# DWS-2_Comutator.net
KiCad netlist of a schematic drawn in Altium Designer
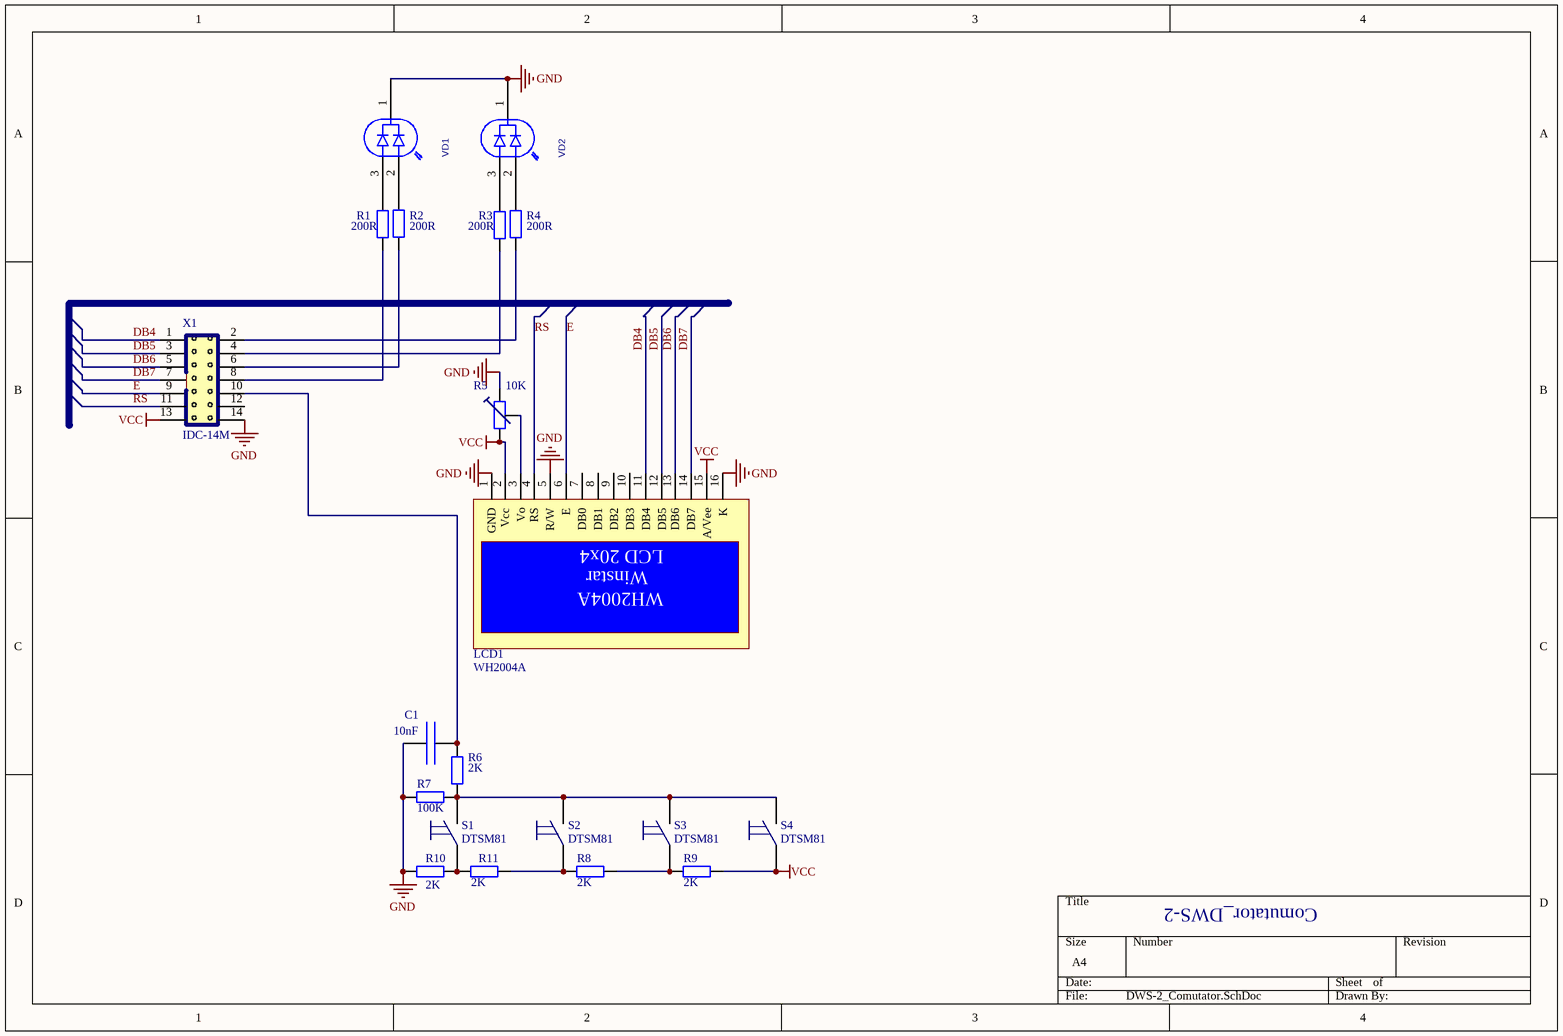
[diagram p0: DWS-2_Comutator.SchDoc]

(export (version "E")
  (design (tool "Eeschema 10.0.6"))
  (components
    (comp (ref "C1")
      (value "10nF")
      (footprint "C0805")
      (description "KONDENS_SMD")
      (libsource (lib "NEW") (part "KONDENS_SMD"))
    )
    (comp (ref "LCD1") (value "WH2004A") (footprint "WH2004A") (libsource (lib "NEW") (part "WH2004A")))
    (comp (ref "R1")
      (value "200R")
      (footprint "C0805")
      (description "Resistor")
      (fields (field (name "Comment") "RES"))
      (libsource (lib "NEW") (part "RES"))
    )
    (comp (ref "R2")
      (value "200R")
      (footprint "C0805")
      (description "Resistor")
      (fields (field (name "Comment") "RES"))
      (libsource (lib "NEW") (part "RES"))
    )
    (comp (ref "R3")
      (value "200R")
      (footprint "C0805")
      (description "Resistor")
      (fields (field (name "Comment") "RES"))
      (libsource (lib "NEW") (part "RES"))
    )
    (comp (ref "R4")
      (value "200R")
      (footprint "C0805")
      (description "Resistor")
      (fields (field (name "Comment") "RES"))
      (libsource (lib "NEW") (part "RES"))
    )
    (comp (ref "R5")
      (value "10K")
      (footprint "CA6V")
      (fields (field (name "Comment") "CA6V"))
      (libsource (lib "NEW") (part "Resistor_podstr"))
    )
    (comp (ref "R6")
      (value "2K")
      (footprint "C0805")
      (description "Resistor")
      (fields (field (name "Comment") "RES"))
      (libsource (lib "NEW") (part "RES"))
    )
    (comp (ref "R7")
      (value "100K")
      (footprint "C0805")
      (description "Resistor")
      (fields (field (name "Comment") "RES"))
      (libsource (lib "") (part "RES_1"))
    )
    (comp (ref "R8")
      (value "2K")
      (footprint "C0805")
      (description "Resistor")
      (fields (field (name "Comment") "RES"))
      (libsource (lib "") (part "RES_1"))
    )
    (comp (ref "R9")
      (value "2K")
      (footprint "C0805")
      (description "Resistor")
      (fields (field (name "Comment") "RES"))
      (libsource (lib "") (part "RES_1"))
    )
    (comp (ref "R10")
      (value "2K")
      (footprint "C0805")
      (description "Resistor")
      (fields (field (name "Comment") "RES"))
      (libsource (lib "") (part "RES_1"))
    )
    (comp (ref "R11")
      (value "2K")
      (footprint "C0805")
      (description "Resistor")
      (fields (field (name "Comment") "RES"))
      (libsource (lib "") (part "RES_1"))
    )
    (comp (ref "S1") (value "DTSM81") (footprint "DTSM81") (libsource (lib "NEW") (part "DTSM81")))
    (comp (ref "S2") (value "DTSM81") (footprint "DTSM81") (libsource (lib "NEW") (part "DTSM81")))
    (comp (ref "S3") (value "DTSM81") (footprint "DTSM81") (libsource (lib "NEW") (part "DTSM81")))
    (comp (ref "S4") (value "DTSM81") (footprint "DTSM81") (libsource (lib "NEW") (part "DTSM81")))
    (comp (ref "VD1")
      (value "LIGHTDIODE2")
      (footprint "LIGHTDIODE2")
      (libsource (lib "NEW") (part "LIGHTDIODE2"))
    )
    (comp (ref "VD2")
      (value "LIGHTDIODE2")
      (footprint "LIGHTDIODE2")
      (libsource (lib "NEW") (part "LIGHTDIODE2"))
    )
    (comp (ref "X1") (value "IDC-14M") (footprint "IDC-14M") (libsource (lib "NEW") (part "IDC-14M")))
  )
  (nets
    (net (code "1") (name "/DB4") (class "Default")
      (node (ref "LCD1") (pin "11") (pinfunction "DB4_11") (pintype "passive"))
      (node (ref "X1") (pin "1") (pintype "passive"))
    )
    (net (code "2") (name "/DB5") (class "Default")
      (node (ref "LCD1") (pin "12") (pinfunction "DB5_12") (pintype "passive"))
      (node (ref "X1") (pin "3") (pintype "passive"))
    )
    (net (code "3") (name "/DB6") (class "Default")
      (node (ref "LCD1") (pin "13") (pinfunction "DB6_13") (pintype "passive"))
      (node (ref "X1") (pin "5") (pintype "passive"))
    )
    (net (code "4") (name "/DB7") (class "Default")
      (node (ref "LCD1") (pin "14") (pinfunction "DB7_14") (pintype "passive"))
      (node (ref "X1") (pin "7") (pintype "passive"))
    )
    (net (code "5") (name "/E") (class "Default")
      (node (ref "LCD1") (pin "6") (pinfunction "E_6") (pintype "passive"))
      (node (ref "X1") (pin "9") (pintype "passive"))
    )
    (net (code "6") (name "/RS") (class "Default")
      (node (ref "LCD1") (pin "4") (pinfunction "RS_4") (pintype "passive"))
      (node (ref "X1") (pin "11") (pintype "passive"))
    )
    (net (code "7") (name "GND") (class "Default")
      (node (ref "C1") (pin "1") (pinfunction "A_1") (pintype "passive"))
      (node (ref "LCD1") (pin "1") (pinfunction "GND_1") (pintype "passive"))
      (node (ref "LCD1") (pin "16") (pinfunction "K_16") (pintype "passive"))
      (node (ref "LCD1") (pin "5") (pinfunction "R/W_5") (pintype "passive"))
      (node (ref "R10") (pin "1") (pinfunction "1_1") (pintype "passive"))
      (node (ref "R5") (pin "1") (pinfunction "1_1") (pintype "passive"))
      (node (ref "R7") (pin "1") (pinfunction "1_1") (pintype "passive"))
      (node (ref "VD1") (pin "1") (pintype "passive"))
      (node (ref "VD2") (pin "1") (pintype "passive"))
      (node (ref "X1") (pin "14") (pintype "passive"))
    )
    (net (code "8") (name "Net-(C1-B)") (class "Default")
      (node (ref "C1") (pin "2") (pinfunction "B_2") (pintype "passive"))
      (node (ref "R6") (pin "2") (pinfunction "2_2") (pintype "passive"))
      (node (ref "X1") (pin "10") (pintype "passive"))
    )
    (net (code "9") (name "Net-(LCD1-Vo)") (class "Default")
      (node (ref "LCD1") (pin "3") (pinfunction "Vo_3") (pintype "passive"))
      (node (ref "R5") (pin "3") (pinfunction "3_3") (pintype "passive"))
    )
    (net (code "10") (name "Net-(R1-Pad1)") (class "Default")
      (node (ref "R1") (pin "1") (pinfunction "1_1") (pintype "passive"))
      (node (ref "X1") (pin "8") (pintype "passive"))
    )
    (net (code "11") (name "Net-(R1-Pad2)") (class "Default")
      (node (ref "R1") (pin "2") (pinfunction "2_2") (pintype "passive"))
      (node (ref "VD1") (pin "3") (pintype "passive"))
    )
    (net (code "12") (name "Net-(R2-Pad1)") (class "Default")
      (node (ref "R2") (pin "1") (pinfunction "1_1") (pintype "passive"))
      (node (ref "X1") (pin "6") (pintype "passive"))
    )
    (net (code "13") (name "Net-(R2-Pad2)") (class "Default")
      (node (ref "R2") (pin "2") (pinfunction "2_2") (pintype "passive"))
      (node (ref "VD1") (pin "2") (pintype "passive"))
    )
    (net (code "14") (name "Net-(R3-Pad1)") (class "Default")
      (node (ref "R3") (pin "1") (pinfunction "1_1") (pintype "passive"))
      (node (ref "X1") (pin "4") (pintype "passive"))
    )
    (net (code "15") (name "Net-(R3-Pad2)") (class "Default")
      (node (ref "R3") (pin "2") (pinfunction "2_2") (pintype "passive"))
      (node (ref "VD2") (pin "3") (pintype "passive"))
    )
    (net (code "16") (name "Net-(R4-Pad1)") (class "Default")
      (node (ref "R4") (pin "1") (pinfunction "1_1") (pintype "passive"))
      (node (ref "X1") (pin "2") (pintype "passive"))
    )
    (net (code "17") (name "Net-(R4-Pad2)") (class "Default")
      (node (ref "R4") (pin "2") (pinfunction "2_2") (pintype "passive"))
      (node (ref "VD2") (pin "2") (pintype "passive"))
    )
    (net (code "18") (name "Net-(R6-Pad1)") (class "Default")
      (node (ref "R6") (pin "1") (pinfunction "1_1") (pintype "passive"))
      (node (ref "R7") (pin "2") (pinfunction "2_2") (pintype "passive"))
      (node (ref "S1") (pin "2") (pinfunction "2_2") (pintype "passive"))
      (node (ref "S2") (pin "2") (pinfunction "2_2") (pintype "passive"))
      (node (ref "S3") (pin "2") (pinfunction "2_2") (pintype "passive"))
      (node (ref "S4") (pin "2") (pinfunction "2_2") (pintype "passive"))
    )
    (net (code "19") (name "Net-(R8-Pad2)") (class "Default")
      (node (ref "R8") (pin "2") (pinfunction "2_2") (pintype "passive"))
      (node (ref "R9") (pin "1") (pinfunction "1_1") (pintype "passive"))
      (node (ref "S3") (pin "1") (pinfunction "1_1") (pintype "passive"))
    )
    (net (code "20") (name "Net-(R10-Pad2)") (class "Default")
      (node (ref "R10") (pin "2") (pinfunction "2_2") (pintype "passive"))
      (node (ref "R11") (pin "1") (pinfunction "1_1") (pintype "passive"))
      (node (ref "S1") (pin "1") (pinfunction "1_1") (pintype "passive"))
    )
    (net (code "21") (name "Net-(R11-Pad2)") (class "Default")
      (node (ref "R11") (pin "2") (pinfunction "2_2") (pintype "passive"))
      (node (ref "R8") (pin "1") (pinfunction "1_1") (pintype "passive"))
      (node (ref "S2") (pin "1") (pinfunction "1_1") (pintype "passive"))
    )
    (net (code "22") (name "VCC") (class "Default")
      (node (ref "LCD1") (pin "15") (pinfunction "A/Vee_15") (pintype "passive"))
      (node (ref "LCD1") (pin "2") (pinfunction "Vcc_2") (pintype "passive"))
      (node (ref "R5") (pin "2") (pinfunction "2_2") (pintype "passive"))
      (node (ref "R9") (pin "2") (pinfunction "2_2") (pintype "passive"))
      (node (ref "S4") (pin "1") (pinfunction "1_1") (pintype "passive"))
      (node (ref "X1") (pin "13") (pintype "passive"))
    )
    (net (code "23") (name "unconnected-(LCD1-DB0-Pad7)") (class "Default")
      (node (ref "LCD1") (pin "7") (pinfunction "DB0_7") (pintype "passive"))
    )
    (net (code "24") (name "unconnected-(LCD1-DB1-Pad8)") (class "Default")
      (node (ref "LCD1") (pin "8") (pinfunction "DB1_8") (pintype "passive"))
    )
    (net (code "25") (name "unconnected-(LCD1-DB2-Pad9)") (class "Default")
      (node (ref "LCD1") (pin "9") (pinfunction "DB2_9") (pintype "passive"))
    )
    (net (code "26") (name "unconnected-(LCD1-DB3-Pad10)") (class "Default")
      (node (ref "LCD1") (pin "10") (pinfunction "DB3_10") (pintype "passive"))
    )
    (net (code "27") (name "unconnected-(X1-Pad12)") (class "Default")
      (node (ref "X1") (pin "12") (pintype "passive"))
    )
  )
)
